# PX_Header.net
KiCad netlist of a schematic drawn in Altium Designer
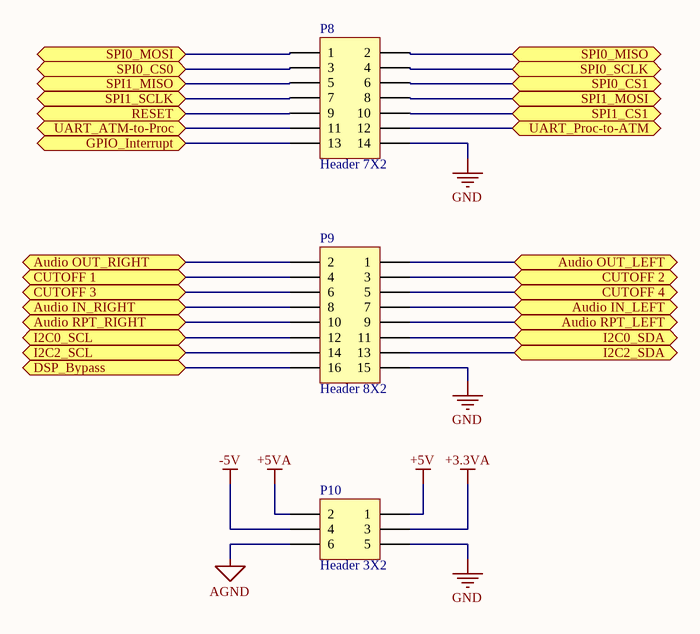
[diagram p0: PX_Header.SchDoc]

(export (version "E")
  (design (tool "Eeschema 10.0.6"))
  (components
    (comp (ref "P8")
      (value "Header 7X2")
      (footprint "Header 14 pins")
      (description "Header, 7-Pin, Dual row")
      (libsource (lib "Miscellaneous Connectors") (part "Header 7X2"))
    )
    (comp (ref "P9")
      (value "Header 8X2")
      (footprint "Header 16 pins")
      (description "Header, 8-Pin, Dual row")
      (libsource (lib "Miscellaneous Connectors") (part "Header 8X2"))
    )
    (comp (ref "P10")
      (value "Header 3X2")
      (footprint "CONN_1241050-3_T")
      (description "Header, 3-Pin, Dual row")
      (libsource (lib "Miscellaneous Connectors") (part "Header 3X2"))
    )
  )
  (nets
    (net (code "1") (name "+3.3VA") (class "Default")
      (node (ref "P10") (pin "3") (pinfunction "3_3") (pintype "passive"))
    )
    (net (code "2") (name "+5V") (class "Default")
      (node (ref "P10") (pin "1") (pinfunction "1_1") (pintype "passive"))
    )
    (net (code "3") (name "+5VA") (class "Default")
      (node (ref "P10") (pin "2") (pinfunction "2_2") (pintype "passive"))
    )
    (net (code "4") (name "-5V") (class "Default")
      (node (ref "P10") (pin "4") (pinfunction "4_4") (pintype "passive"))
    )
    (net (code "5") (name "/Audio IN_LEFT") (class "Default")
      (node (ref "P9") (pin "7") (pinfunction "7_7") (pintype "passive"))
    )
    (net (code "6") (name "/Audio IN_RIGHT") (class "Default")
      (node (ref "P9") (pin "8") (pinfunction "8_8") (pintype "passive"))
    )
    (net (code "7") (name "/Audio OUT_LEFT") (class "Default")
      (node (ref "P9") (pin "1") (pinfunction "1_1") (pintype "passive"))
    )
    (net (code "8") (name "/Audio OUT_RIGHT") (class "Default")
      (node (ref "P9") (pin "2") (pinfunction "2_2") (pintype "passive"))
    )
    (net (code "9") (name "/Audio RPT_LEFT") (class "Default")
      (node (ref "P9") (pin "9") (pinfunction "9_9") (pintype "passive"))
    )
    (net (code "10") (name "/Audio RPT_RIGHT") (class "Default")
      (node (ref "P9") (pin "10") (pinfunction "10_10") (pintype "passive"))
    )
    (net (code "11") (name "/CUTOFF 1") (class "Default")
      (node (ref "P9") (pin "4") (pinfunction "4_4") (pintype "passive"))
    )
    (net (code "12") (name "/CUTOFF 2") (class "Default")
      (node (ref "P9") (pin "3") (pinfunction "3_3") (pintype "passive"))
    )
    (net (code "13") (name "/CUTOFF 3") (class "Default")
      (node (ref "P9") (pin "6") (pinfunction "6_6") (pintype "passive"))
    )
    (net (code "14") (name "/CUTOFF 4") (class "Default")
      (node (ref "P9") (pin "5") (pinfunction "5_5") (pintype "passive"))
    )
    (net (code "15") (name "/DSP_Bypass") (class "Default")
      (node (ref "P9") (pin "16") (pinfunction "16_16") (pintype "passive"))
    )
    (net (code "16") (name "/GPIO_Interrupt") (class "Default")
      (node (ref "P8") (pin "13") (pinfunction "13_13") (pintype "passive"))
    )
    (net (code "17") (name "/I2C0_SCL") (class "Default")
      (node (ref "P9") (pin "12") (pinfunction "12_12") (pintype "passive"))
    )
    (net (code "18") (name "/I2C0_SDA") (class "Default")
      (node (ref "P9") (pin "11") (pinfunction "11_11") (pintype "passive"))
    )
    (net (code "19") (name "/I2C2_SCL") (class "Default")
      (node (ref "P9") (pin "14") (pinfunction "14_14") (pintype "passive"))
    )
    (net (code "20") (name "/I2C2_SDA") (class "Default")
      (node (ref "P9") (pin "13") (pinfunction "13_13") (pintype "passive"))
    )
    (net (code "21") (name "/RESET") (class "Default")
      (node (ref "P8") (pin "9") (pinfunction "9_9") (pintype "passive"))
    )
    (net (code "22") (name "/SPI0_CS0") (class "Default")
      (node (ref "P8") (pin "3") (pinfunction "3_3") (pintype "passive"))
    )
    (net (code "23") (name "/SPI0_CS1") (class "Default")
      (node (ref "P8") (pin "6") (pinfunction "6_6") (pintype "passive"))
    )
    (net (code "24") (name "/SPI0_MISO") (class "Default")
      (node (ref "P8") (pin "2") (pinfunction "2_2") (pintype "passive"))
    )
    (net (code "25") (name "/SPI0_MOSI") (class "Default")
      (node (ref "P8") (pin "1") (pinfunction "1_1") (pintype "passive"))
    )
    (net (code "26") (name "/SPI0_SCLK") (class "Default")
      (node (ref "P8") (pin "4") (pinfunction "4_4") (pintype "passive"))
    )
    (net (code "27") (name "/SPI1_CS1") (class "Default")
      (node (ref "P8") (pin "10") (pinfunction "10_10") (pintype "passive"))
    )
    (net (code "28") (name "/SPI1_MISO") (class "Default")
      (node (ref "P8") (pin "5") (pinfunction "5_5") (pintype "passive"))
    )
    (net (code "29") (name "/SPI1_MOSI") (class "Default")
      (node (ref "P8") (pin "8") (pinfunction "8_8") (pintype "passive"))
    )
    (net (code "30") (name "/SPI1_SCLK") (class "Default")
      (node (ref "P8") (pin "7") (pinfunction "7_7") (pintype "passive"))
    )
    (net (code "31") (name "/UART_ATM-to-Proc") (class "Default")
      (node (ref "P8") (pin "11") (pinfunction "11_11") (pintype "passive"))
    )
    (net (code "32") (name "/UART_Proc-to-ATM") (class "Default")
      (node (ref "P8") (pin "12") (pinfunction "12_12") (pintype "passive"))
    )
    (net (code "33") (name "AGND") (class "Default")
      (node (ref "P10") (pin "6") (pinfunction "6_6") (pintype "passive"))
    )
    (net (code "34") (name "GND") (class "Default")
      (node (ref "P10") (pin "5") (pinfunction "5_5") (pintype "passive"))
      (node (ref "P8") (pin "14") (pinfunction "14_14") (pintype "passive"))
      (node (ref "P9") (pin "15") (pinfunction "15_15") (pintype "passive"))
    )
  )
)
